# DS1307_DS1338-v12.net
KiCad netlist of a schematic drawn in EAGLE
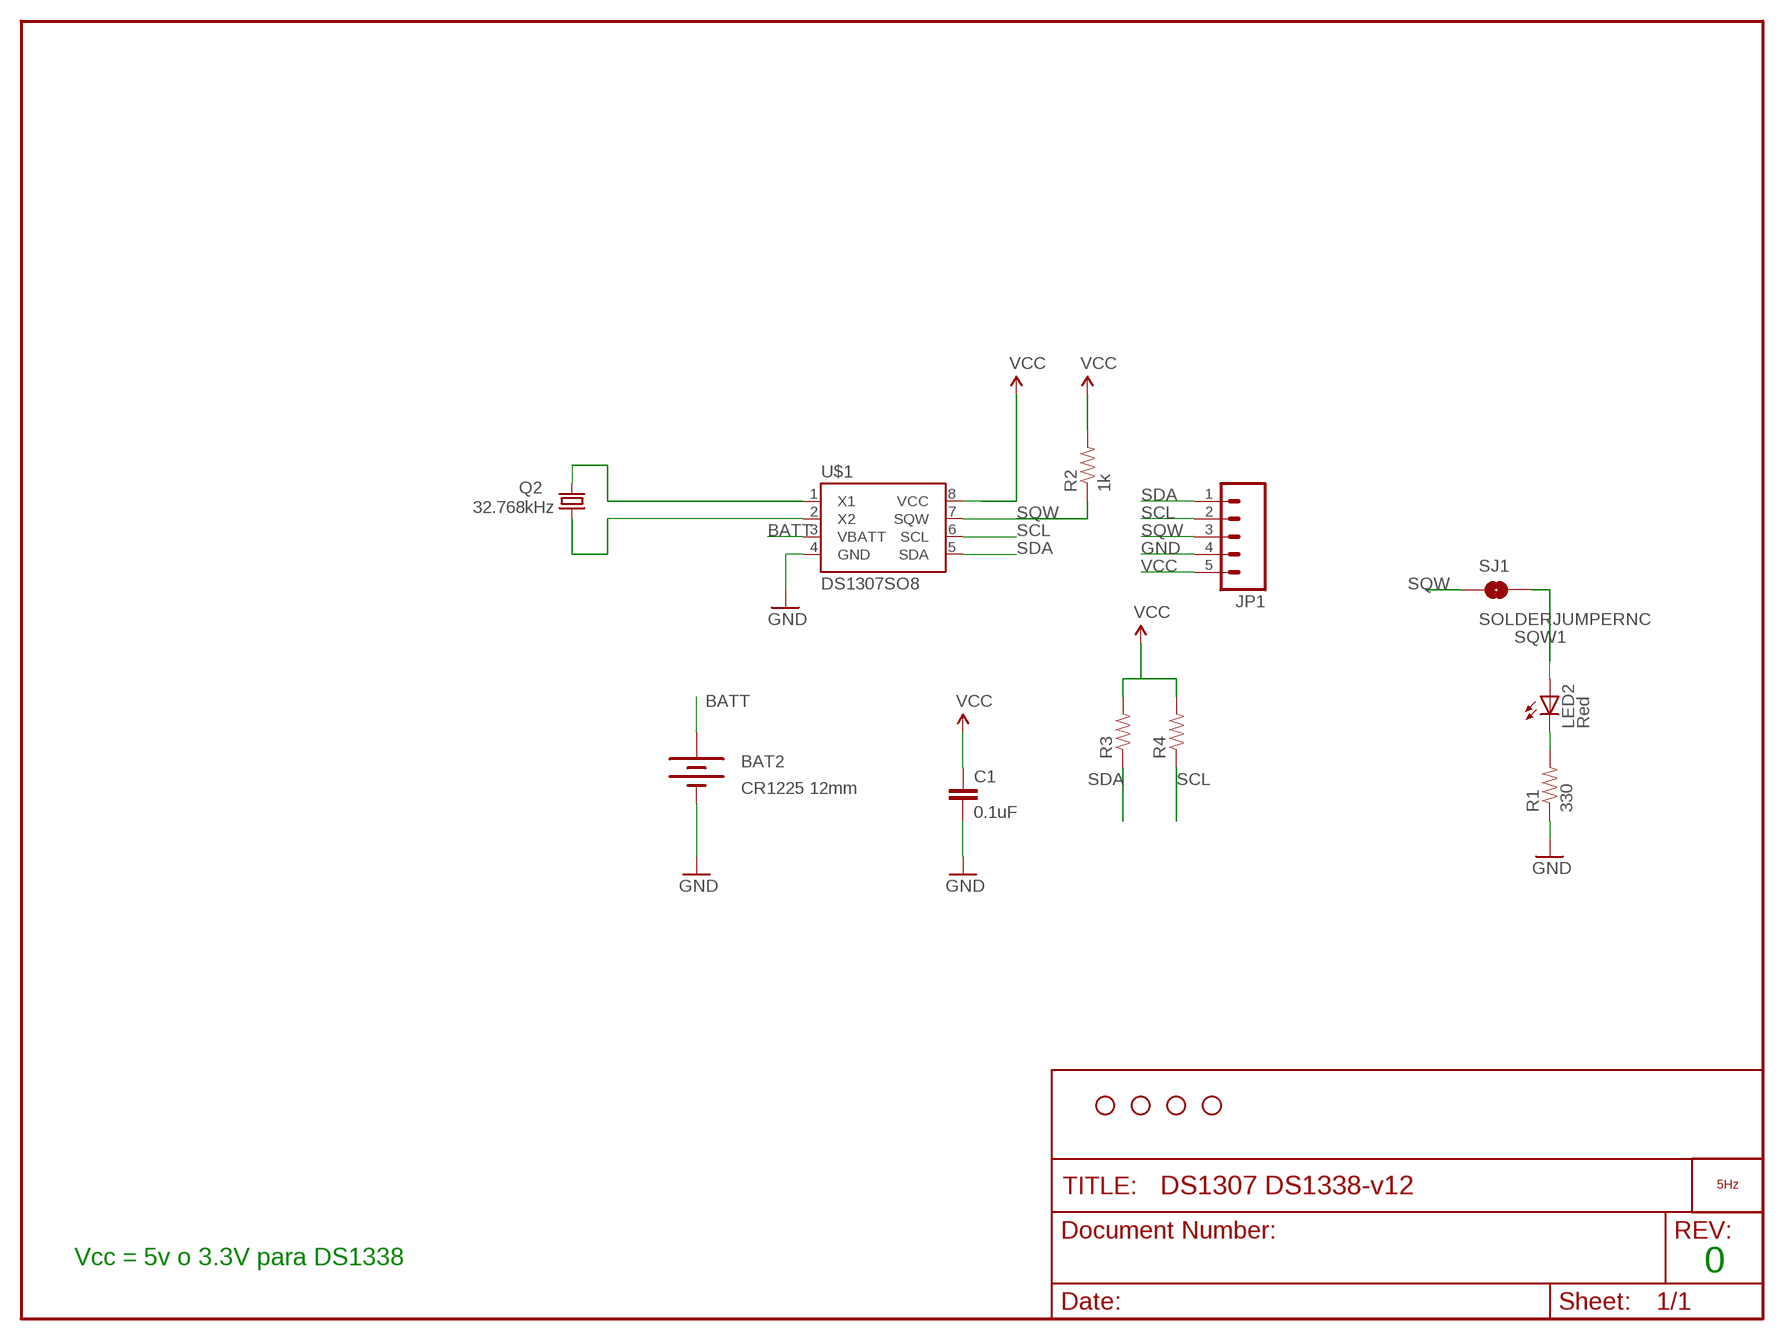
[diagram p0: schematic, sheet 1]

(export (version "E")
  (design (tool "Eeschema 10.0.6"))
  (components
    (comp (ref "BAT2")
      (value "CR1225 12mm")
      (footprint "eagle-import:BATTCON_12MM_PTH")
      (libsource (lib "eagle-import") (part "BATTERY12PTH"))
    )
    (comp (ref "C1")
      (value "0.1uF")
      (footprint "eagle-import:0603-CAP")
      (libsource (lib "eagle-import") (part "CAP0603-CAP"))
    )
    (comp (ref "JP1")
      (value "M05PTH")
      (footprint "eagle-import:1X05")
      (libsource (lib "eagle-import") (part "M05PTH"))
    )
    (comp (ref "JP2")
      (value "STAND-OFF")
      (footprint "eagle-import:STAND-OFF")
      (libsource (lib "eagle-import") (part "STAND-OFF"))
    )
    (comp (ref "JP3")
      (value "STAND-OFF")
      (footprint "eagle-import:STAND-OFF")
      (libsource (lib "eagle-import") (part "STAND-OFF"))
    )
    (comp (ref "JP4")
      (value "STAND-OFF")
      (footprint "eagle-import:STAND-OFF")
      (libsource (lib "eagle-import") (part "STAND-OFF"))
    )
    (comp (ref "JP7")
      (value "STAND-OFF")
      (footprint "eagle-import:STAND-OFF")
      (libsource (lib "eagle-import") (part "STAND-OFF"))
    )
    (comp (ref "LED2")
      (value "Red")
      (footprint "eagle-import:LED-0603")
      (libsource (lib "eagle-import") (part "LED0603"))
    )
    (comp (ref "LOGO1")
      (value "LOGO_5HZ_MAIN_5MM")
      (footprint "eagle-import:5HZ_LOGO_MAIN_5MM")
      (libsource (lib "eagle-import") (part "LOGO_5HZ_MAIN_5MM"))
    )
    (comp (ref "Q2")
      (value "32.768kHz")
      (footprint "eagle-import:CRYSTAL-32KHZ-SMD")
      (libsource (lib "eagle-import") (part "CRYSTAL32-SMD"))
    )
    (comp (ref "R1")
      (value "330")
      (footprint "eagle-import:0603-RES")
      (libsource (lib "eagle-import") (part "RESISTOR0603-RES"))
    )
    (comp (ref "R2")
      (value "1k")
      (footprint "eagle-import:0603-RES")
      (libsource (lib "eagle-import") (part "RESISTOR0603-RES"))
    )
    (comp (ref "R3")
      (value "RESISTORPTH-1/6W")
      (footprint "eagle-import:1_6W-RES")
      (libsource (lib "eagle-import") (part "RESISTORPTH-1/6W"))
    )
    (comp (ref "R4")
      (value "RESISTORPTH-1/6W")
      (footprint "eagle-import:1_6W-RES")
      (libsource (lib "eagle-import") (part "RESISTORPTH-1/6W"))
    )
    (comp (ref "SJ1")
      (value "SOLDERJUMPERNC")
      (footprint "eagle-import:SJ_2S")
      (libsource (lib "eagle-import") (part "SOLDERJUMPERNC"))
    )
    (comp (ref "U$1")
      (value "DS1307SO8")
      (footprint "eagle-import:SO08")
      (libsource (lib "eagle-import") (part "DS1307SO8"))
    )
  )
  (nets
    (net (code "1") (name "/BATT") (class "Default")
      (node (ref "BAT2") (pin "VCC@1") (pinfunction "+_VCC@1") (pintype "power_in"))
      (node (ref "U$1") (pin "3") (pinfunction "VBATT_3") (pintype "bidirectional"))
    )
    (net (code "2") (name "/SCL") (class "Default")
      (node (ref "JP1") (pin "2") (pinfunction "2_2") (pintype "passive"))
      (node (ref "R4") (pin "1") (pinfunction "1_1") (pintype "passive"))
      (node (ref "U$1") (pin "6") (pinfunction "SCL_6") (pintype "bidirectional"))
    )
    (net (code "3") (name "/SDA") (class "Default")
      (node (ref "JP1") (pin "1") (pinfunction "1_1") (pintype "passive"))
      (node (ref "R3") (pin "1") (pinfunction "1_1") (pintype "passive"))
      (node (ref "U$1") (pin "5") (pinfunction "SDA_5") (pintype "bidirectional"))
    )
    (net (code "4") (name "/SQW") (class "Default")
      (node (ref "JP1") (pin "3") (pinfunction "3_3") (pintype "passive"))
      (node (ref "R2") (pin "1") (pinfunction "1_1") (pintype "passive"))
      (node (ref "SJ1") (pin "1") (pinfunction "1_1") (pintype "passive"))
      (node (ref "U$1") (pin "7") (pinfunction "SQW_7") (pintype "bidirectional"))
    )
    (net (code "5") (name "/SQW1") (class "Default")
      (node (ref "LED2") (pin "A") (pinfunction "A_A") (pintype "passive"))
      (node (ref "SJ1") (pin "2") (pinfunction "2_2") (pintype "passive"))
    )
    (net (code "6") (name "GND") (class "Default")
      (node (ref "BAT2") (pin "GND") (pinfunction "-_GND") (pintype "power_in"))
      (node (ref "C1") (pin "2") (pinfunction "2_2") (pintype "passive"))
      (node (ref "JP1") (pin "4") (pinfunction "4_4") (pintype "passive"))
      (node (ref "R1") (pin "1") (pinfunction "1_1") (pintype "passive"))
      (node (ref "U$1") (pin "4") (pinfunction "GND_4") (pintype "bidirectional"))
    )
    (net (code "7") (name "Net-(LED2-PadC)") (class "Default")
      (node (ref "LED2") (pin "C") (pinfunction "C_C") (pintype "passive"))
      (node (ref "R1") (pin "2") (pinfunction "2_2") (pintype "passive"))
    )
    (net (code "8") (name "Net-(Q2-1)") (class "Default")
      (node (ref "Q2") (pin "X1") (pinfunction "1_X1") (pintype "passive"))
      (node (ref "U$1") (pin "2") (pinfunction "X2_2") (pintype "bidirectional"))
    )
    (net (code "9") (name "Net-(Q2-2)") (class "Default")
      (node (ref "Q2") (pin "X2") (pinfunction "2_X2") (pintype "passive"))
      (node (ref "U$1") (pin "1") (pinfunction "X1_1") (pintype "bidirectional"))
    )
    (net (code "10") (name "VCC") (class "Default")
      (node (ref "C1") (pin "1") (pinfunction "1_1") (pintype "passive"))
      (node (ref "JP1") (pin "5") (pinfunction "5_5") (pintype "passive"))
      (node (ref "R2") (pin "2") (pinfunction "2_2") (pintype "passive"))
      (node (ref "R3") (pin "2") (pinfunction "2_2") (pintype "passive"))
      (node (ref "R4") (pin "2") (pinfunction "2_2") (pintype "passive"))
      (node (ref "U$1") (pin "8") (pinfunction "VCC_8") (pintype "bidirectional"))
    )
  )
)
